# TopLevel.net
KiCad netlist of a schematic drawn in Altium Designer
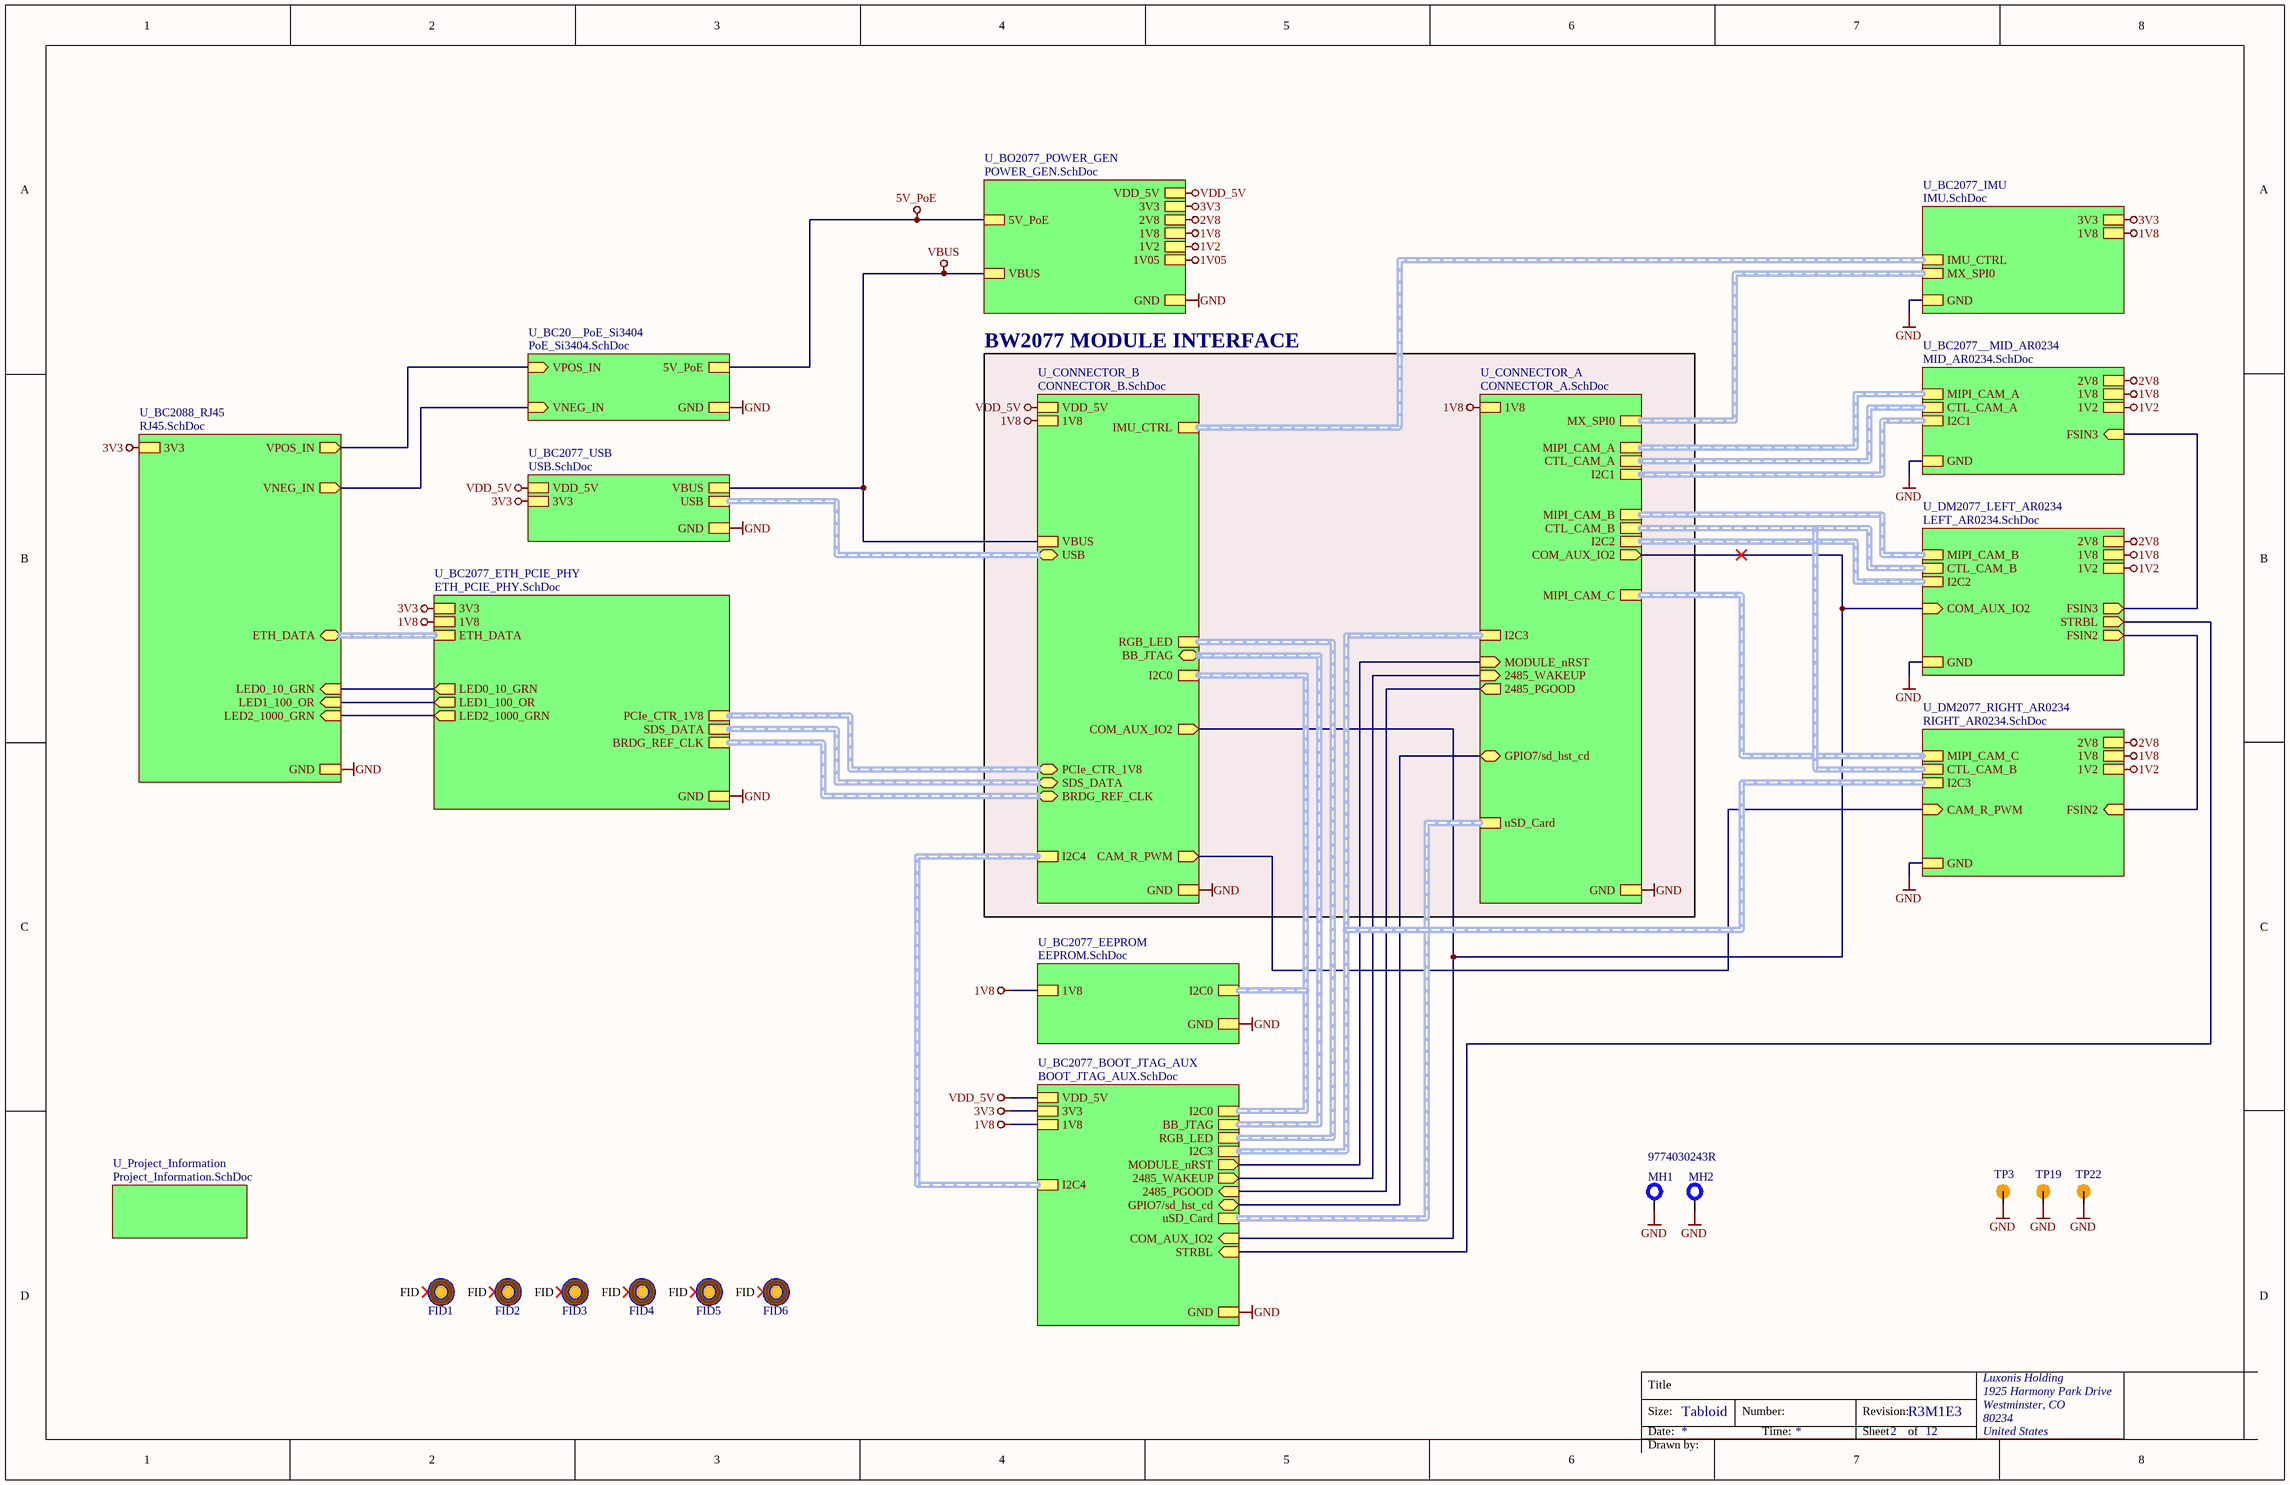
[diagram p0: TopLevel.SchDoc]

(export (version "E")
  (design (tool "Eeschema 10.0.6"))
  (components
    (comp (ref "FID1")
      (value "FIDUCIAL")
      (footprint "FIDUCIAL_ROUND_1MM")
      (description "Fiducial with various available footprints")
      (libsource (lib "Luxonis LLC") (part "FIDUCIAL"))
    )
    (comp (ref "FID2")
      (value "FIDUCIAL")
      (footprint "FIDUCIAL_ROUND_1MM")
      (description "Fiducial with various available footprints")
      (libsource (lib "Luxonis LLC") (part "FIDUCIAL"))
    )
    (comp (ref "FID3")
      (value "FIDUCIAL")
      (footprint "FIDUCIAL_ROUND_1MM")
      (description "Fiducial with various available footprints")
      (libsource (lib "Luxonis LLC") (part "FIDUCIAL"))
    )
    (comp (ref "FID4")
      (value "FIDUCIAL")
      (footprint "FIDUCIAL_ROUND_1MM")
      (description "Fiducial with various available footprints")
      (libsource (lib "Luxonis LLC") (part "FIDUCIAL"))
    )
    (comp (ref "FID5")
      (value "FIDUCIAL")
      (footprint "FIDUCIAL_ROUND_1MM")
      (description "Fiducial with various available footprints")
      (libsource (lib "Luxonis LLC") (part "FIDUCIAL"))
    )
    (comp (ref "FID6")
      (value "FIDUCIAL")
      (footprint "FIDUCIAL_ROUND_1MM")
      (description "Fiducial with various available footprints")
      (libsource (lib "Luxonis LLC") (part "FIDUCIAL"))
    )
    (comp (ref "MH1")
      (value "9774030243R")
      (footprint "9774030243R")
      (description "MP ROUND STANDOFF M2X0.4 STEEL 3MM")
      (libsource (lib "Luxonis LLC") (part "9774030243R"))
    )
    (comp (ref "MH2")
      (value "9774030243R")
      (footprint "9774030243R")
      (description "MP ROUND STANDOFF M2X0.4 STEEL 3MM")
      (libsource (lib "Luxonis LLC") (part "9774030243R"))
    )
    (comp (ref "TP3")
      (value "TEST_POINT")
      (footprint "TP100_200_NS")
      (libsource (lib "Luxonis LLC") (part "TEST_POINT"))
    )
    (comp (ref "TP19")
      (value "TEST_POINT")
      (footprint "TP100_200_NS")
      (libsource (lib "Luxonis LLC") (part "TEST_POINT"))
    )
    (comp (ref "TP22")
      (value "TEST_POINT")
      (footprint "TP100_200_NS")
      (libsource (lib "Luxonis LLC") (part "TEST_POINT"))
    )
  )
  (nets
    (net (code "41") (name "GND") (class "Default")
      (node (ref "MH1") (pin "1") (pintype "passive"))
      (node (ref "MH2") (pin "1") (pintype "passive"))
      (node (ref "TP19") (pin "1") (pintype "passive"))
      (node (ref "TP22") (pin "1") (pintype "passive"))
      (node (ref "TP3") (pin "1") (pintype "passive"))
    )
    (net (code "44") (name "unconnected-(FID1-PadFID)") (class "Default")
      (node (ref "FID1") (pin "FID") (pinfunction "FID_FID") (pintype "input+no_connect"))
    )
    (net (code "45") (name "unconnected-(FID2-PadFID)") (class "Default")
      (node (ref "FID2") (pin "FID") (pinfunction "FID_FID") (pintype "input+no_connect"))
    )
    (net (code "46") (name "unconnected-(FID3-PadFID)") (class "Default")
      (node (ref "FID3") (pin "FID") (pinfunction "FID_FID") (pintype "input+no_connect"))
    )
    (net (code "47") (name "unconnected-(FID4-PadFID)") (class "Default")
      (node (ref "FID4") (pin "FID") (pinfunction "FID_FID") (pintype "input+no_connect"))
    )
    (net (code "48") (name "unconnected-(FID5-PadFID)") (class "Default")
      (node (ref "FID5") (pin "FID") (pinfunction "FID_FID") (pintype "input+no_connect"))
    )
    (net (code "49") (name "unconnected-(FID6-PadFID)") (class "Default")
      (node (ref "FID6") (pin "FID") (pinfunction "FID_FID") (pintype "input+no_connect"))
    )
  )
)
